# DE-150824.net
KiCad netlist of a schematic drawn in Altium Designer
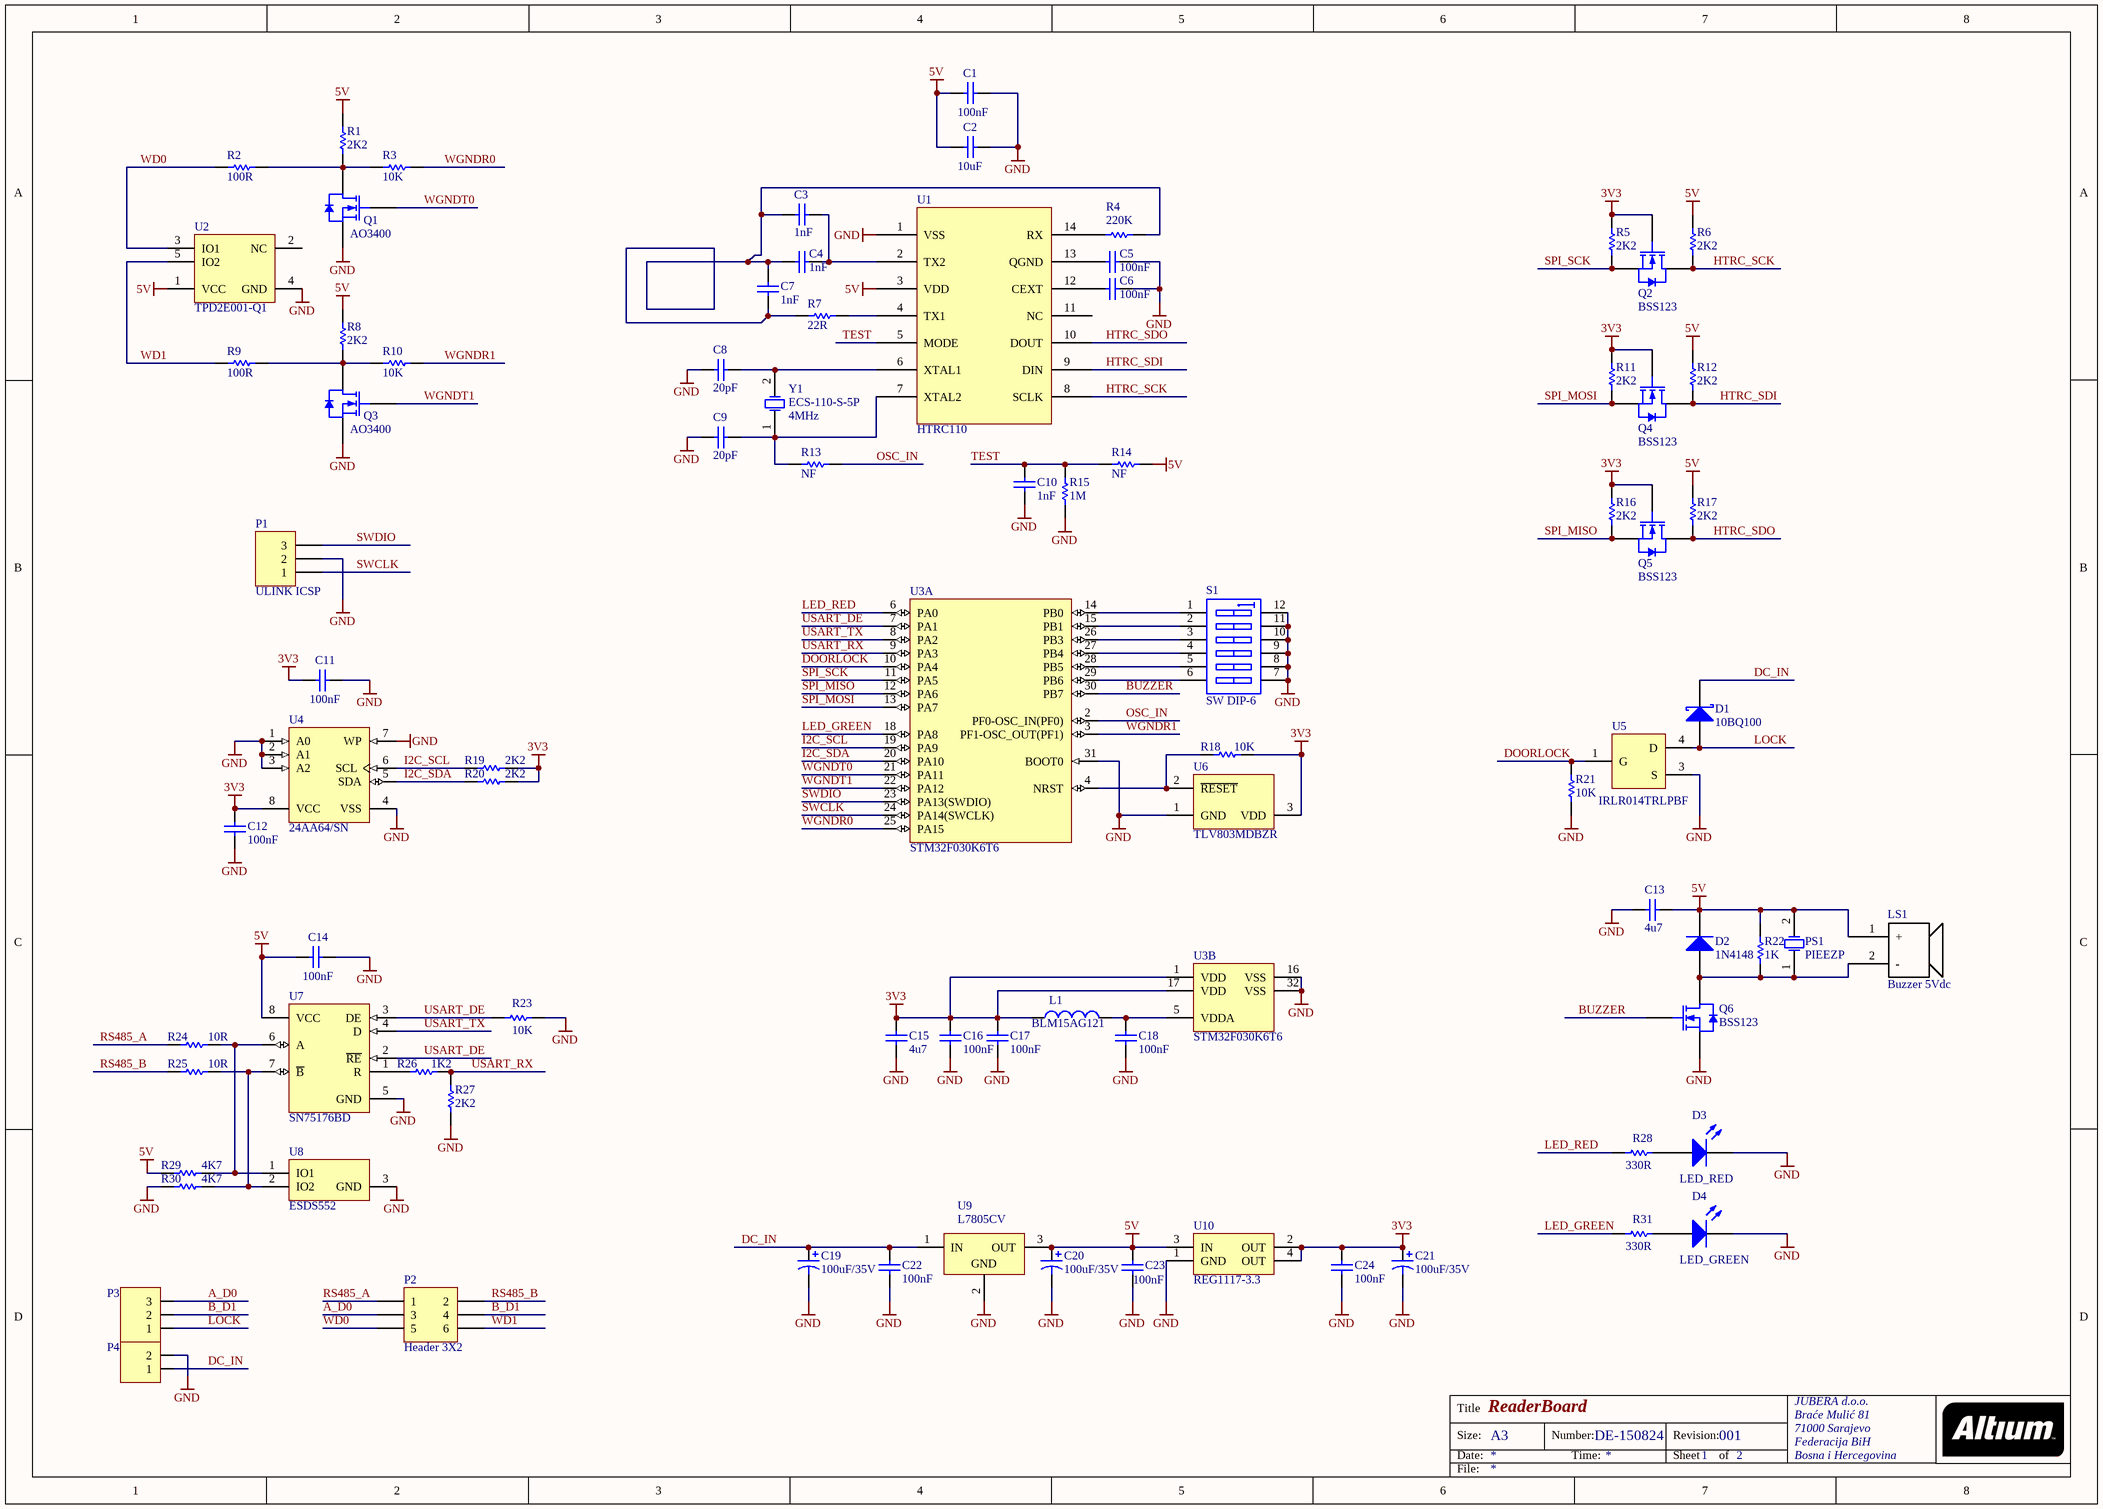
[diagram p0: DE-150824.SchDoc]

(export (version "E")
  (design (tool "Eeschema 10.0.6"))
  (components
    (comp (ref "C1")
      (value "100nF")
      (footprint "0603")
      (description "Ceramic Chip Capacitor - Standard")
      (fields (field (name "Comment") "C0603") (field (name "PUBLISHER") "Altium Limited"))
      (libsource (lib "DE-150824") (part "C0603"))
    )
    (comp (ref "C2")
      (value "10uF")
      (footprint "0805")
      (description "Ceramic Chip Capacitor - Standard")
      (fields (field (name "Comment") "C0805") (field (name "PUBLISHER") "Altium Limited"))
      (libsource (lib "DE-150824") (part "C0805"))
    )
    (comp (ref "C3")
      (value "1nF")
      (footprint "VP31-2.5")
      (description "Dipped Radial Multilayer Ceramic Capacitor COG (NPO): 1pF, 50/63V")
      (fields (field (name "PUBLISHER") "Altium Limited"))
      (libsource (lib "Vishay Vitramon Ceramic Dipped Capacitor") (part "VP31BA1R0CA"))
    )
    (comp (ref "C4")
      (value "1nF")
      (footprint "0805")
      (description "Ceramic Chip Capacitor - Standard")
      (fields (field (name "Comment") "C0805") (field (name "PUBLISHER") "Altium Limited"))
      (libsource (lib "DE-150824") (part "C0805"))
    )
    (comp (ref "C5")
      (value "100nF")
      (footprint "0603")
      (description "Ceramic Chip Capacitor - Standard")
      (fields (field (name "Comment") "C0603") (field (name "PUBLISHER") "Altium Limited"))
      (libsource (lib "DE-150824") (part "C0603"))
    )
    (comp (ref "C6")
      (value "100nF")
      (footprint "0603")
      (description "Ceramic Chip Capacitor - Standard")
      (fields (field (name "Comment") "C0603") (field (name "PUBLISHER") "Altium Limited"))
      (libsource (lib "DE-150824") (part "C0603"))
    )
    (comp (ref "C7")
      (value "1nF")
      (footprint "0805")
      (description "Ceramic Chip Capacitor - Standard")
      (fields (field (name "Comment") "C0805") (field (name "PUBLISHER") "Altium Limited"))
      (libsource (lib "DE-150824") (part "C0805"))
    )
    (comp (ref "C8")
      (value "20pF")
      (footprint "0603")
      (description "Ceramic Chip Capacitor - Standard")
      (fields (field (name "PUBLISHER") "Altium Limited"))
      (libsource (lib "KEMET Chip Capacitor") (part "C0603"))
    )
    (comp (ref "C9")
      (value "20pF")
      (footprint "0603")
      (description "Ceramic Chip Capacitor - Standard")
      (fields (field (name "PUBLISHER") "Altium Limited"))
      (libsource (lib "KEMET Chip Capacitor") (part "C0603"))
    )
    (comp (ref "C10")
      (value "1nF")
      (footprint "0603")
      (description "Ceramic Chip Capacitor - Standard")
      (fields (field (name "Comment") "C0603") (field (name "PUBLISHER") "Altium Limited"))
      (libsource (lib "DE-150824") (part "C0603"))
    )
    (comp (ref "C11")
      (value "100nF")
      (footprint "0603")
      (description "Ceramic Chip Capacitor - Standard")
      (fields (field (name "Comment") "C0603") (field (name "PUBLISHER") "Altium Limited"))
      (libsource (lib "DE-150824") (part "C0603"))
    )
    (comp (ref "C12")
      (value "100nF")
      (footprint "0603")
      (description "Ceramic Chip Capacitor - Standard")
      (fields (field (name "Comment") "C0603") (field (name "PUBLISHER") "Altium Limited"))
      (libsource (lib "DE-150824") (part "C0603"))
    )
    (comp (ref "C13")
      (value "4u7")
      (footprint "0805")
      (description "Ceramic Chip Capacitor - Standard")
      (fields (field (name "Comment") "C0805") (field (name "PUBLISHER") "Altium Limited"))
      (libsource (lib "DE-150824") (part "C0805"))
    )
    (comp (ref "C14")
      (value "100nF")
      (footprint "0603")
      (description "Ceramic Chip Capacitor - Standard")
      (fields (field (name "Comment") "C0603") (field (name "PUBLISHER") "Altium Limited"))
      (libsource (lib "DE-150824") (part "C0603"))
    )
    (comp (ref "C15")
      (value "4u7")
      (footprint "0805")
      (description "Ceramic Chip Capacitor - Standard")
      (fields (field (name "Comment") "C0805") (field (name "PUBLISHER") "Altium Limited"))
      (libsource (lib "DE-150824") (part "C0805"))
    )
    (comp (ref "C16")
      (value "100nF")
      (footprint "0603")
      (description "Ceramic Chip Capacitor - Standard")
      (fields (field (name "Comment") "C0603") (field (name "PUBLISHER") "Altium Limited"))
      (libsource (lib "DE-150824") (part "C0603"))
    )
    (comp (ref "C17")
      (value "100nF")
      (footprint "0603")
      (description "Ceramic Chip Capacitor - Standard")
      (fields (field (name "Comment") "C0603") (field (name "PUBLISHER") "Altium Limited"))
      (libsource (lib "DE-150824") (part "C0603"))
    )
    (comp (ref "C18")
      (value "100nF")
      (footprint "0603")
      (description "Ceramic Chip Capacitor - Standard")
      (fields (field (name "Comment") "C0603") (field (name "PUBLISHER") "Altium Limited"))
      (libsource (lib "DE-150824") (part "C0603"))
    )
    (comp (ref "C19")
      (value "100uF/35V")
      (footprint "F")
      (fields (field (name "PUBLISHER") "Altium Limited"))
      (libsource (lib "Vishay Sprague Tantalum Chip Capacitor") (part "194D106X0015F2"))
    )
    (comp (ref "C20")
      (value "100uF/35V")
      (footprint "F")
      (fields (field (name "PUBLISHER") "Altium Limited"))
      (libsource (lib "Vishay Sprague Tantalum Chip Capacitor") (part "194D106X0015F2"))
    )
    (comp (ref "C21")
      (value "100uF/35V")
      (footprint "F")
      (fields (field (name "PUBLISHER") "Altium Limited"))
      (libsource (lib "Vishay Sprague Tantalum Chip Capacitor") (part "194D106X0015F2"))
    )
    (comp (ref "C22")
      (value "100nF")
      (footprint "0603")
      (description "Ceramic Chip Capacitor - Standard")
      (fields (field (name "Comment") "C0603") (field (name "PUBLISHER") "Altium Limited"))
      (libsource (lib "DE-150824") (part "C0603"))
    )
    (comp (ref "C23")
      (value "100nF")
      (footprint "0603")
      (description "Ceramic Chip Capacitor - Standard")
      (fields (field (name "Comment") "C0603") (field (name "PUBLISHER") "Altium Limited"))
      (libsource (lib "DE-150824") (part "C0603"))
    )
    (comp (ref "C24")
      (value "100nF")
      (footprint "0603")
      (description "Ceramic Chip Capacitor - Standard")
      (fields (field (name "Comment") "C0603") (field (name "PUBLISHER") "Altium Limited"))
      (libsource (lib "DE-150824") (part "C0603"))
    )
    (comp (ref "D1")
      (value "10BQ100")
      (footprint "SMB")
      (description "Schottky Rectifier")
      (fields (field (name "PUBLISHER") "Altium Limited"))
      (libsource (lib "DE-150824") (part "10BQ100"))
    )
    (comp (ref "D2")
      (value "1N4148")
      (footprint "SOD323")
      (description "General-purpose Diode")
      (fields (field (name "PUBLISHER") "Altium Limited"))
      (libsource (lib "DE-150824") (part "BAS321"))
    )
    (comp (ref "D3")
      (value "LED_RED")
      (footprint "1.6X0.8X0.8")
      (description "Blue Surface Mount Chip LED, Blue")
      (fields (field (name "PUBLISHER") "Altium Limited"))
      (libsource (lib "DE-150824") (part "HSMB-C190"))
    )
    (comp (ref "D4")
      (value "LED_GREEN")
      (footprint "1.6X0.8X0.8")
      (description "Blue Surface Mount Chip LED, Blue")
      (fields (field (name "PUBLISHER") "Altium Limited"))
      (libsource (lib "DE-150824") (part "HSMB-C190"))
    )
    (comp (ref "L1")
      (value "BLM15AG121")
      (footprint "0402-A")
      (description "SMD chip inductor")
      (fields (field (name "PUBLISHER") "Altium Limited"))
      (libsource (lib "DE-150824") (part "Chip inductor"))
    )
    (comp (ref "LS1")
      (value "Buzzer 5Vdc")
      (footprint "BUZZER")
      (description "5Vdc PCB buzzer")
      (libsource (lib "DE-150824") (part "BUZZER"))
    )
    (comp (ref "P1")
      (value "ULINK ICSP")
      (footprint "HDR1X3")
      (description "Header, 3-Pin")
      (fields (field (name "PUBLISHER") "Altium Limited"))
      (libsource (lib "DE-150824") (part "Header 3"))
    )
    (comp (ref "P2")
      (value "Header 3X2")
      (footprint "HDR2X3")
      (description "Header, 3-Pin, Dual row")
      (fields (field (name "PUBLISHER") "Altium Limited"))
      (libsource (lib "Miscellaneous Connectors") (part "Header 3X2"))
    )
    (comp (ref "P3")
      (value "3 pin terminal")
      (footprint "3 PIN TERMINAL BLOCK  3,5mm")
      (description "3 pinski terminal blok konektor")
      (libsource (lib "DE-150824") (part "TERMINAL BLOK 3"))
    )
    (comp (ref "P4")
      (value "2 pin terminal")
      (footprint "2 PIN TERMINAL BLOCK 3,5mm")
      (description "Terminal blok konektor 3,5 mm")
      (libsource (lib "DE-150824") (part "TERMINAL BLOK 2"))
    )
    (comp (ref "PS1")
      (value "PIEEZP")
      (footprint "PKM13EPYH4000-A0")
      (description "Surface Mount Quartz Crystal")
      (fields (field (name "PUBLISHER") "Altium Limited"))
      (libsource (lib "DE-150824") (part "PKM13EPYH4000-A0"))
    )
    (comp (ref "Q1")
      (value "AO3400")
      (footprint "SOT23_N")
      (description "N-channel Enhancement Mode Vertical D-MOSFET")
      (fields (field (name "PUBLISHER") "Altium Limited"))
      (libsource (lib "DE-150824") (part "BSS123"))
    )
    (comp (ref "Q2")
      (value "BSS123")
      (footprint "SOT23_N")
      (description "N-channel Enhancement Mode Vertical D-MOSFET")
      (fields (field (name "PUBLISHER") "Altium Limited"))
      (libsource (lib "DE-150824") (part "BSS123"))
    )
    (comp (ref "Q3")
      (value "AO3400")
      (footprint "SOT23_N")
      (description "N-channel Enhancement Mode Vertical D-MOSFET")
      (fields (field (name "PUBLISHER") "Altium Limited"))
      (libsource (lib "DE-150824") (part "BSS123"))
    )
    (comp (ref "Q4")
      (value "BSS123")
      (footprint "SOT23_N")
      (description "N-channel Enhancement Mode Vertical D-MOSFET")
      (fields (field (name "PUBLISHER") "Altium Limited"))
      (libsource (lib "DE-150824") (part "BSS123"))
    )
    (comp (ref "Q5")
      (value "BSS123")
      (footprint "SOT23_N")
      (description "N-channel Enhancement Mode Vertical D-MOSFET")
      (fields (field (name "PUBLISHER") "Altium Limited"))
      (libsource (lib "DE-150824") (part "BSS123"))
    )
    (comp (ref "Q6")
      (value "BSS123")
      (footprint "SOT23_N")
      (description "N-channel Enhancement Mode Vertical D-MOSFET")
      (fields (field (name "PUBLISHER") "Altium Limited"))
      (libsource (lib "DE-150824") (part "BSS123"))
    )
    (comp (ref "R1")
      (value "2K2")
      (footprint "ERA-0805")
      (fields (field (name "PUBLISHER") "Altium Limited"))
      (libsource (lib "DE-150824") (part "ERAS"))
    )
    (comp (ref "R2")
      (value "100R")
      (footprint "ERA-0805")
      (fields (field (name "PUBLISHER") "Altium Limited"))
      (libsource (lib "DE-150824") (part "ERAS"))
    )
    (comp (ref "R3")
      (value "10K")
      (footprint "ERA-0805")
      (fields (field (name "PUBLISHER") "Altium Limited"))
      (libsource (lib "DE-150824") (part "ERAS"))
    )
    (comp (ref "R4")
      (value "220K")
      (footprint "ERA-0805")
      (fields (field (name "PUBLISHER") "Altium Limited"))
      (libsource (lib "DE-150824") (part "ERAS"))
    )
    (comp (ref "R5")
      (value "2K2")
      (footprint "ERA-0603")
      (fields (field (name "PUBLISHER") "Altium Limited"))
      (libsource (lib "DE-150824") (part "ERAV"))
    )
    (comp (ref "R6")
      (value "2K2")
      (footprint "ERA-0603")
      (fields (field (name "PUBLISHER") "Altium Limited"))
      (libsource (lib "DE-150824") (part "ERAV"))
    )
    (comp (ref "R7")
      (value "22R")
      (footprint "ERA-0805")
      (fields (field (name "PUBLISHER") "Altium Limited"))
      (libsource (lib "DE-150824") (part "ERAS"))
    )
    (comp (ref "R8")
      (value "2K2")
      (footprint "ERA-0805")
      (fields (field (name "PUBLISHER") "Altium Limited"))
      (libsource (lib "DE-150824") (part "ERAS"))
    )
    (comp (ref "R9")
      (value "100R")
      (footprint "ERA-0805")
      (fields (field (name "PUBLISHER") "Altium Limited"))
      (libsource (lib "DE-150824") (part "ERAS"))
    )
    (comp (ref "R10")
      (value "10K")
      (footprint "ERA-0805")
      (fields (field (name "PUBLISHER") "Altium Limited"))
      (libsource (lib "DE-150824") (part "ERAS"))
    )
    (comp (ref "R11")
      (value "2K2")
      (footprint "ERA-0603")
      (fields (field (name "PUBLISHER") "Altium Limited"))
      (libsource (lib "DE-150824") (part "ERAV"))
    )
    (comp (ref "R12")
      (value "2K2")
      (footprint "ERA-0603")
      (fields (field (name "PUBLISHER") "Altium Limited"))
      (libsource (lib "DE-150824") (part "ERAV"))
    )
    (comp (ref "R13")
      (value "NF")
      (footprint "ERA-0805")
      (fields (field (name "PUBLISHER") "Altium Limited"))
      (libsource (lib "DE-150824") (part "ERAS"))
    )
    (comp (ref "R14")
      (value "NF")
      (footprint "ERA-0805")
      (fields (field (name "PUBLISHER") "Altium Limited"))
      (libsource (lib "DE-150824") (part "ERAS"))
    )
    (comp (ref "R15")
      (value "1M")
      (footprint "ERA-0805")
      (fields (field (name "PUBLISHER") "Altium Limited"))
      (libsource (lib "DE-150824") (part "ERAS"))
    )
    (comp (ref "R16")
      (value "2K2")
      (footprint "ERA-0603")
      (fields (field (name "PUBLISHER") "Altium Limited"))
      (libsource (lib "DE-150824") (part "ERAV"))
    )
    (comp (ref "R17")
      (value "2K2")
      (footprint "ERA-0603")
      (fields (field (name "PUBLISHER") "Altium Limited"))
      (libsource (lib "DE-150824") (part "ERAV"))
    )
    (comp (ref "R18")
      (value "10K")
      (footprint "ERA-0603")
      (fields (field (name "PUBLISHER") "Altium Limited"))
      (libsource (lib "DE-150824") (part "ERAV"))
    )
    (comp (ref "R19")
      (value "2K2")
      (footprint "ERA-0603")
      (fields (field (name "PUBLISHER") "Altium Limited"))
      (libsource (lib "DE-150824") (part "ERAV"))
    )
    (comp (ref "R20")
      (value "2K2")
      (footprint "ERA-0603")
      (fields (field (name "PUBLISHER") "Altium Limited"))
      (libsource (lib "DE-150824") (part "ERAV"))
    )
    (comp (ref "R21")
      (value "10K")
      (footprint "ERA-0603")
      (fields (field (name "PUBLISHER") "Altium Limited"))
      (libsource (lib "DE-150824") (part "ERAV"))
    )
    (comp (ref "R22")
      (value "1K")
      (footprint "ERA-0603")
      (fields (field (name "PUBLISHER") "Altium Limited"))
      (libsource (lib "DE-150824") (part "ERAV"))
    )
    (comp (ref "R23")
      (value "10K")
      (footprint "ERA-0603")
      (fields (field (name "PUBLISHER") "Altium Limited"))
      (libsource (lib "DE-150824") (part "ERAV"))
    )
    (comp (ref "R24")
      (value "10R")
      (footprint "ERA-0805")
      (fields (field (name "PUBLISHER") "Altium Limited"))
      (libsource (lib "DE-150824") (part "ERAS"))
    )
    (comp (ref "R25")
      (value "10R")
      (footprint "ERA-0805")
      (fields (field (name "PUBLISHER") "Altium Limited"))
      (libsource (lib "DE-150824") (part "ERAS"))
    )
    (comp (ref "R26")
      (value "1K2")
      (footprint "ERA-0603")
      (fields (field (name "PUBLISHER") "Altium Limited"))
      (libsource (lib "DE-150824") (part "ERAV"))
    )
    (comp (ref "R27")
      (value "2K2")
      (footprint "ERA-0603")
      (fields (field (name "PUBLISHER") "Altium Limited"))
      (libsource (lib "DE-150824") (part "ERAV"))
    )
    (comp (ref "R28")
      (value "330R")
      (footprint "ERA-0603")
      (fields (field (name "PUBLISHER") "Altium Limited"))
      (libsource (lib "DE-150824") (part "ERAV"))
    )
    (comp (ref "R29")
      (value "4K7")
      (footprint "ERA-0603")
      (fields (field (name "PUBLISHER") "Altium Limited"))
      (libsource (lib "DE-150824") (part "ERAV"))
    )
    (comp (ref "R30")
      (value "4K7")
      (footprint "ERA-0603")
      (fields (field (name "PUBLISHER") "Altium Limited"))
      (libsource (lib "DE-150824") (part "ERAV"))
    )
    (comp (ref "R31")
      (value "330R")
      (footprint "ERA-0603")
      (fields (field (name "PUBLISHER") "Altium Limited"))
      (libsource (lib "DE-150824") (part "ERAV"))
    )
    (comp (ref "S1")
      (value "SW DIP-6")
      (footprint "DIP-12/SW")
      (description "DIP Switch, 6 Position, SPST")
      (fields (field (name "PUBLISHER") "Altium Limited"))
      (libsource (lib "Miscellaneous Devices") (part "SW DIP-6"))
    )
    (comp (ref "U1")
      (value "HTRC110")
      (footprint "SOIC-SL14_N")
      (description "HITAG reader chip")
      (libsource (lib "DE-150824") (part "HTRC110"))
    )
    (comp (ref "U2")
      (value "TPD2E001-Q1")
      (footprint "DRL5_V")
      (fields (field (name "MANUFACTURER") "Texas Instruments") (field (name "PARTNUMBER") "TPD2E001IDRLRQ1"))
      (libsource (lib "TI Interface ESD EMI Protection") (part "TPD2E001IDRLRQ1"))
    )
    (comp (ref "U3")
      (value "STM32F030K6T6")
      (footprint "STM-LQFP32_N")
      (libsource (lib "STMicroelectronics STM32 F0") (part "STM32F030K6T6"))
    )
    (comp (ref "U4")
      (value "24AA64/SN")
      (footprint "SOIC-SN8_N")
      (description "64Kbit, 400kHz, 1.7V, I2C Serial EEPROM, 8-Pin SOIC 150mil, Commercial Temperature")
      (fields (field (name "PUBLISHER") "Altium Limited"))
      (libsource (lib "DE-150824") (part "24AA64/SN"))
    )
    (comp (ref "U5")
      (value "IRLR014TRLPBF")
      (footprint "ONSC-DPAK-3-369C-01_V")
      (fields (field (name "MANUFACTURER") "On Semiconductor") (field (name "PARTNUMBER") "NCV8408DTRKG"))
      (libsource (lib "ON Semi Protected MOSFETs") (part "NCV8408DTRKG"))
    )
    (comp (ref "U6")
      (value "TLV803MDBZR")
      (footprint "DBZ3_N")
      (fields (field (name "MANUFACTURER") "Texas Instruments"))
      (libsource (lib "TI Power Management Supervisor and Reset IC") (part "TLV803MDBZR"))
    )
    (comp (ref "U7")
      (value "SN75176BD")
      (footprint "D008_N")
      (description "Differential Bus Transceiver")
      (fields (field (name "PUBLISHER") "Altium Limited"))
      (libsource (lib "DE-150824") (part "SN75176BD"))
    )
    (comp (ref "U8")
      (value "ESDS552")
      (footprint "DCK3_N")
      (fields (field (name "MANUFACTURER") "Texas Instruments") (field (name "PARTNUMBER") "TPD2E007DCKR"))
      (libsource (lib "TI Interface ESD EMI Protection") (part "TPD2E007DCKR"))
    )
    (comp (ref "U9")
      (value "L7805CV")
      (footprint "TO220")
      (description "Positive Voltage Regulator, 5V, 3-Pin TO-220")
      (libsource (lib "DE-150824") (part "L7805CV"))
    )
    (comp (ref "U10")
      (value "REG1117-3.3")
      (footprint "ZZ311")
      (description "800mA and 1A Low Dropout Positive Regulator 2.85V, 3.3V, 5V, and Adjustable")
      (fields (field (name "PUBLISHER") "Altium Limited"))
      (libsource (lib "DE-080324") (part "REG1117-3.3"))
    )
    (comp (ref "Y1")
      (value "ECS-110-S-5P")
      (footprint "CSM-7")
      (description "Crystal Oscillator")
      (fields (field (name "ALTIUM_VALUE") "4MHz") (field (name "PUBLISHER") "Altium Limited"))
      (libsource (lib "ECS Crystal Oscillator") (part "ECS-110-S-5P"))
    )
  )
  (nets
    (net (code "1") (name "/A_D0") (class "Default")
      (node (ref "P2") (pin "3") (pinfunction "3_3") (pintype "passive"))
      (node (ref "P3") (pin "3") (pinfunction "3_3") (pintype "passive"))
    )
    (net (code "2") (name "/BUZZER") (class "Default")
      (node (ref "Q6") (pin "1") (pinfunction "G_1") (pintype "passive"))
      (node (ref "U3") (pin "30") (pinfunction "PB7_30") (pintype "bidirectional"))
    )
    (net (code "3") (name "/B_D1") (class "Default")
      (node (ref "P2") (pin "4") (pinfunction "4_4") (pintype "passive"))
      (node (ref "P3") (pin "2") (pinfunction "2_2") (pintype "passive"))
    )
    (net (code "4") (name "/DC_IN") (class "Default")
      (node (ref "C19") (pin "1") (pinfunction "1_1") (pintype "passive"))
      (node (ref "C22") (pin "2") (pinfunction "2_2") (pintype "passive"))
      (node (ref "D1") (pin "2") (pinfunction "K_2") (pintype "passive"))
      (node (ref "P4") (pin "1") (pinfunction "1_1") (pintype "passive"))
      (node (ref "U9") (pin "1") (pinfunction "IN_1") (pintype "power_in"))
    )
    (net (code "5") (name "/DOORLOCK") (class "Default")
      (node (ref "R21") (pin "1") (pinfunction "1_1") (pintype "passive"))
      (node (ref "U3") (pin "10") (pinfunction "PA4_10") (pintype "bidirectional"))
      (node (ref "U5") (pin "1") (pinfunction "G_1") (pintype "passive"))
    )
    (net (code "6") (name "/HTRC_SCK") (class "Default")
      (node (ref "Q2") (pin "3") (pinfunction "D_3") (pintype "passive"))
      (node (ref "R6") (pin "1") (pinfunction "1_1") (pintype "passive"))
      (node (ref "U1") (pin "8") (pinfunction "SCLK_8") (pintype "passive"))
    )
    (net (code "7") (name "/HTRC_SDI") (class "Default")
      (node (ref "Q4") (pin "3") (pinfunction "D_3") (pintype "passive"))
      (node (ref "R12") (pin "1") (pinfunction "1_1") (pintype "passive"))
      (node (ref "U1") (pin "9") (pinfunction "DIN_9") (pintype "passive"))
    )
    (net (code "8") (name "/HTRC_SDO") (class "Default")
      (node (ref "Q5") (pin "3") (pinfunction "D_3") (pintype "passive"))
      (node (ref "R17") (pin "1") (pinfunction "1_1") (pintype "passive"))
      (node (ref "U1") (pin "10") (pinfunction "DOUT_10") (pintype "passive"))
    )
    (net (code "9") (name "/I2C_SCL") (class "Default")
      (node (ref "R19") (pin "1") (pinfunction "1_1") (pintype "passive"))
      (node (ref "U3") (pin "19") (pinfunction "PA9_19") (pintype "bidirectional"))
      (node (ref "U4") (pin "6") (pinfunction "SCL_6") (pintype "input"))
    )
    (net (code "10") (name "/I2C_SDA") (class "Default")
      (node (ref "R20") (pin "1") (pinfunction "1_1") (pintype "passive"))
      (node (ref "U3") (pin "20") (pinfunction "PA10_20") (pintype "bidirectional"))
      (node (ref "U4") (pin "5") (pinfunction "SDA_5") (pintype "bidirectional"))
    )
    (net (code "11") (name "/LED_GREEN") (class "Default")
      (node (ref "R31") (pin "1") (pinfunction "1_1") (pintype "passive"))
      (node (ref "U3") (pin "18") (pinfunction "PA8_18") (pintype "bidirectional"))
    )
    (net (code "12") (name "/LED_RED") (class "Default")
      (node (ref "R28") (pin "1") (pinfunction "1_1") (pintype "passive"))
      (node (ref "U3") (pin "6") (pinfunction "PA0_6") (pintype "bidirectional"))
    )
    (net (code "13") (name "/LOCK") (class "Default")
      (node (ref "D1") (pin "1") (pinfunction "A_1") (pintype "passive"))
      (node (ref "P3") (pin "1") (pinfunction "1_1") (pintype "passive"))
      (node (ref "U5") (pin "4") (pinfunction "D_4") (pintype "passive"))
    )
    (net (code "14") (name "/OSC_IN") (class "Default")
      (node (ref "R13") (pin "2") (pinfunction "2_2") (pintype "passive"))
      (node (ref "U3") (pin "2") (pinfunction "PF0-OSC_IN(PF0)_2") (pintype "bidirectional"))
    )
    (net (code "15") (name "/RS485_A") (class "Default")
      (node (ref "P2") (pin "1") (pinfunction "1_1") (pintype "passive"))
      (node (ref "R24") (pin "1") (pinfunction "1_1") (pintype "passive"))
    )
    (net (code "16") (name "/RS485_B") (class "Default")
      (node (ref "P2") (pin "2") (pinfunction "2_2") (pintype "passive"))
      (node (ref "R25") (pin "1") (pinfunction "1_1") (pintype "passive"))
    )
    (net (code "17") (name "/SPI_MISO") (class "Default")
      (node (ref "Q5") (pin "2") (pinfunction "S_2") (pintype "passive"))
      (node (ref "R16") (pin "1") (pinfunction "1_1") (pintype "passive"))
      (node (ref "U3") (pin "12") (pinfunction "PA6_12") (pintype "bidirectional"))
    )
    (net (code "18") (name "/SPI_MOSI") (class "Default")
      (node (ref "Q4") (pin "2") (pinfunction "S_2") (pintype "passive"))
      (node (ref "R11") (pin "1") (pinfunction "1_1") (pintype "passive"))
      (node (ref "U3") (pin "13") (pinfunction "PA7_13") (pintype "bidirectional"))
    )
    (net (code "19") (name "/SPI_SCK") (class "Default")
      (node (ref "Q2") (pin "2") (pinfunction "S_2") (pintype "passive"))
      (node (ref "R5") (pin "1") (pinfunction "1_1") (pintype "passive"))
      (node (ref "U3") (pin "11") (pinfunction "PA5_11") (pintype "bidirectional"))
    )
    (net (code "20") (name "/SWCLK") (class "Default")
      (node (ref "P1") (pin "1") (pinfunction "1_1") (pintype "passive"))
      (node (ref "U3") (pin "24") (pinfunction "PA14(SWCLK)_24") (pintype "bidirectional"))
    )
    (net (code "21") (name "/SWDIO") (class "Default")
      (node (ref "P1") (pin "3") (pinfunction "3_3") (pintype "passive"))
      (node (ref "U3") (pin "23") (pinfunction "PA13(SWDIO)_23") (pintype "bidirectional"))
    )
    (net (code "22") (name "/TEST") (class "Default")
      (node (ref "C10") (pin "1") (pinfunction "1_1") (pintype "passive"))
      (node (ref "R14") (pin "1") (pinfunction "1_1") (pintype "passive"))
      (node (ref "R15") (pin "2") (pinfunction "2_2") (pintype "passive"))
      (node (ref "U1") (pin "5") (pinfunction "MODE_5") (pintype "passive"))
    )
    (net (code "23") (name "/USART_DE") (class "Default")
      (node (ref "R23") (pin "1") (pinfunction "1_1") (pintype "passive"))
      (node (ref "U3") (pin "7") (pinfunction "PA1_7") (pintype "bidirectional"))
      (node (ref "U7") (pin "2") (pinfunction "~{RE}_2") (pintype "input"))
      (node (ref "U7") (pin "3") (pinfunction "DE_3") (pintype "input"))
    )
    (net (code "24") (name "/USART_RX") (class "Default")
      (node (ref "R26") (pin "2") (pinfunction "2_2") (pintype "passive"))
      (node (ref "R27") (pin "2") (pinfunction "2_2") (pintype "passive"))
      (node (ref "U3") (pin "9") (pinfunction "PA3_9") (pintype "bidirectional"))
    )
    (net (code "25") (name "/USART_TX") (class "Default")
      (node (ref "U3") (pin "8") (pinfunction "PA2_8") (pintype "bidirectional"))
      (node (ref "U7") (pin "4") (pinfunction "D_4") (pintype "input"))
    )
    (net (code "26") (name "/WD0") (class "Default")
      (node (ref "P2") (pin "5") (pinfunction "5_5") (pintype "passive"))
      (node (ref "R2") (pin "2") (pinfunction "2_2") (pintype "passive"))
      (node (ref "U2") (pin "3") (pinfunction "IO1_3") (pintype "passive"))
    )
    (net (code "27") (name "/WD1") (class "Default")
      (node (ref "P2") (pin "6") (pinfunction "6_6") (pintype "passive"))
      (node (ref "R9") (pin "2") (pinfunction "2_2") (pintype "passive"))
      (node (ref "U2") (pin "5") (pinfunction "IO2_5") (pintype "passive"))
    )
    (net (code "28") (name "/WGNDR0") (class "Default")
      (node (ref "R3") (pin "1") (pinfunction "1_1") (pintype "passive"))
      (node (ref "U3") (pin "25") (pinfunction "PA15_25") (pintype "bidirectional"))
    )
    (net (code "29") (name "/WGNDR1") (class "Default")
      (node (ref "R10") (pin "1") (pinfunction "1_1") (pintype "passive"))
      (node (ref "U3") (pin "3") (pinfunction "PF1-OSC_OUT(PF1)_3") (pintype "bidirectional"))
    )
    (net (code "30") (name "/WGNDT0") (class "Default")
      (node (ref "Q1") (pin "1") (pinfunction "G_1") (pintype "passive"))
      (node (ref "U3") (pin "21") (pinfunction "PA11_21") (pintype "bidirectional"))
    )
    (net (code "31") (name "/WGNDT1") (class "Default")
      (node (ref "Q3") (pin "1") (pinfunction "G_1") (pintype "passive"))
      (node (ref "U3") (pin "22") (pinfunction "PA12_22") (pintype "bidirectional"))
    )
    (net (code "32") (name "3V3") (class "Default")
      (node (ref "C11") (pin "2") (pinfunction "2_2") (pintype "passive"))
      (node (ref "C12") (pin "2") (pinfunction "2_2") (pintype "passive"))
      (node (ref "C15") (pin "2") (pinfunction "2_2") (pintype "passive"))
      (node (ref "C16") (pin "2") (pinfunction "2_2") (pintype "passive"))
      (node (ref "C17") (pin "2") (pinfunction "2_2") (pintype "passive"))
      (node (ref "C21") (pin "1") (pinfunction "1_1") (pintype "passive"))
      (node (ref "C24") (pin "2") (pinfunction "2_2") (pintype "passive"))
      (node (ref "L1") (pin "1") (pinfunction "1_1") (pintype "passive"))
      (node (ref "Q2") (pin "1") (pinfunction "G_1") (pintype "passive"))
      (node (ref "Q4") (pin "1") (pinfunction "G_1") (pintype "passive"))
      (node (ref "Q5") (pin "1") (pinfunction "G_1") (pintype "passive"))
      (node (ref "R11") (pin "2") (pinfunction "2_2") (pintype "passive"))
      (node (ref "R16") (pin "2") (pinfunction "2_2") (pintype "passive"))
      (node (ref "R18") (pin "1") (pinfunction "1_1") (pintype "passive"))
      (node (ref "R19") (pin "2") (pinfunction "2_2") (pintype "passive"))
      (node (ref "R20") (pin "2") (pinfunction "2_2") (pintype "passive"))
      (node (ref "R5") (pin "2") (pinfunction "2_2") (pintype "passive"))
      (node (ref "U10") (pin "2") (pinfunction "OUT_2") (pintype "power_in"))
      (node (ref "U10") (pin "4") (pinfunction "OUT_4") (pintype "power_in"))
      (node (ref "U3") (pin "1") (pinfunction "VDD_1") (pintype "power_in"))
      (node (ref "U3") (pin "17") (pinfunction "VDD_17") (pintype "power_in"))
      (node (ref "U4") (pin "8") (pinfunction "VCC_8") (pintype "power_in"))
      (node (ref "U6") (pin "3") (pinfunction "VDD_3") (pintype "power_in"))
    )
    (net (code "33") (name "5V") (class "Default")
      (node (ref "C1") (pin "2") (pinfunction "2_2") (pintype "passive"))
      (node (ref "C13") (pin "1") (pinfunction "1_1") (pintype "passive"))
      (node (ref "C14") (pin "2") (pinfunction "2_2") (pintype "passive"))
      (node (ref "C2") (pin "2") (pinfunction "2_2") (pintype "passive"))
      (node (ref "C20") (pin "1") (pinfunction "1_1") (pintype "passive"))
      (node (ref "C23") (pin "2") (pinfunction "2_2") (pintype "passive"))
      (node (ref "D2") (pin "1") (pinfunction "K_1") (pintype "passive"))
      (node (ref "LS1") (pin "1") (pinfunction "+_1") (pintype "passive"))
      (node (ref "PS1") (pin "2") (pinfunction "OSC2_2") (pintype "passive"))
      (node (ref "R1") (pin "2") (pinfunction "2_2") (pintype "passive"))
      (node (ref "R12") (pin "2") (pinfunction "2_2") (pintype "passive"))
      (node (ref "R14") (pin "2") (pinfunction "2_2") (pintype "passive"))
      (node (ref "R17") (pin "2") (pinfunction "2_2") (pintype "passive"))
      (node (ref "R22") (pin "1") (pinfunction "1_1") (pintype "passive"))
      (node (ref "R29") (pin "1") (pinfunction "1_1") (pintype "passive"))
      (node (ref "R6") (pin "2") (pinfunction "2_2") (pintype "passive"))
      (node (ref "R8") (pin "2") (pinfunction "2_2") (pintype "passive"))
      (node (ref "U1") (pin "3") (pinfunction "VDD_3") (pintype "passive"))
      (node (ref "U10") (pin "3") (pinfunction "IN_3") (pintype "power_in"))
      (node (ref "U2") (pin "1") (pinfunction "VCC_1") (pintype "power_in"))
      (node (ref "U7") (pin "8") (pinfunction "VCC_8") (pintype "power_in"))
      (node (ref "U9") (pin "3") (pinfunction "OUT_3") (pintype "power_in"))
    )
    (net (code "34") (name "GND") (class "Default")
      (node (ref "C1") (pin "1") (pinfunction "1_1") (pintype "passive"))
      (node (ref "C10") (pin "2") (pinfunction "2_2") (pintype "passive"))
      (node (ref "C11") (pin "1") (pinfunction "1_1") (pintype "passive"))
      (node (ref "C12") (pin "1") (pinfunction "1_1") (pintype "passive"))
      (node (ref "C13") (pin "2") (pinfunction "2_2") (pintype "passive"))
      (node (ref "C14") (pin "1") (pinfunction "1_1") (pintype "passive"))
      (node (ref "C15") (pin "1") (pinfunction "1_1") (pintype "passive"))
      (node (ref "C16") (pin "1") (pinfunction "1_1") (pintype "passive"))
      (node (ref "C17") (pin "1") (pinfunction "1_1") (pintype "passive"))
      (node (ref "C18") (pin "1") (pinfunction "1_1") (pintype "passive"))
      (node (ref "C19") (pin "2") (pinfunction "2_2") (pintype "passive"))
      (node (ref "C2") (pin "1") (pinfunction "1_1") (pintype "passive"))
      (node (ref "C20") (pin "2") (pinfunction "2_2") (pintype "passive"))
      (node (ref "C21") (pin "2") (pinfunction "2_2") (pintype "passive"))
      (node (ref "C22") (pin "1") (pinfunction "1_1") (pintype "passive"))
      (node (ref "C23") (pin "1") (pinfunction "1_1") (pintype "passive"))
      (node (ref "C24") (pin "1") (pinfunction "1_1") (pintype "passive"))
      (node (ref "C5") (pin "1") (pinfunction "1_1") (pintype "passive"))
      (node (ref "C6") (pin "1") (pinfunction "1_1") (pintype "passive"))
      (node (ref "C8") (pin "1") (pinfunction "1_1") (pintype "passive"))
      (node (ref "C9") (pin "1") (pinfunction "1_1") (pintype "passive"))
      (node (ref "D3") (pin "2") (pinfunction "K_2") (pintype "passive"))
      (node (ref "D4") (pin "2") (pinfunction "K_2") (pintype "passive"))
      (node (ref "P1") (pin "2") (pinfunction "2_2") (pintype "passive"))
      (node (ref "P4") (pin "2") (pinfunction "2_2") (pintype "passive"))
      (node (ref "Q1") (pin "2") (pinfunction "S_2") (pintype "passive"))
      (node (ref "Q3") (pin "2") (pinfunction "S_2") (pintype "passive"))
      (node (ref "Q6") (pin "2") (pinfunction "S_2") (pintype "passive"))
      (node (ref "R15") (pin "1") (pinfunction "1_1") (pintype "passive"))
      (node (ref "R21") (pin "2") (pinfunction "2_2") (pintype "passive"))
      (node (ref "R23") (pin "2") (pinfunction "2_2") (pintype "passive"))
      (node (ref "R27") (pin "1") (pinfunction "1_1") (pintype "passive"))
      (node (ref "R30") (pin "1") (pinfunction "1_1") (pintype "passive"))
      (node (ref "S1") (pin "10") (pinfunction "B3_10") (pintype "passive"))
      (node (ref "S1") (pin "11") (pinfunction "B2_11") (pintype "passive"))
      (node (ref "S1") (pin "12") (pinfunction "B1_12") (pintype "passive"))
      (node (ref "S1") (pin "7") (pinfunction "B6_7") (pintype "passive"))
      (node (ref "S1") (pin "8") (pinfunction "B5_8") (pintype "passive"))
      (node (ref "S1") (pin "9") (pinfunction "B4_9") (pintype "passive"))
      (node (ref "U1") (pin "1") (pinfunction "VSS_1") (pintype "passive"))
      (node (ref "U10") (pin "1") (pinfunction "GND_1") (pintype "power_in"))
      (node (ref "U2") (pin "4") (pinfunction "GND_4") (pintype "power_in"))
      (node (ref "U3") (pin "16") (pinfunction "VSS_16") (pintype "power_in"))
      (node (ref "U3") (pin "31") (pinfunction "BOOT0_31") (pintype "input"))
      (node (ref "U3") (pin "32") (pinfunction "VSS_32") (pintype "power_in"))
      (node (ref "U4") (pin "1") (pinfunction "A0_1") (pintype "input"))
      (node (ref "U4") (pin "2") (pinfunction "A1_2") (pintype "input"))
      (node (ref "U4") (pin "3") (pinfunction "A2_3") (pintype "input"))
      (node (ref "U4") (pin "4") (pinfunction "VSS_4") (pintype "power_in"))
      (node (ref "U4") (pin "7") (pinfunction "WP_7") (pintype "input"))
      (node (ref "U5") (pin "3") (pinfunction "S_3") (pintype "passive"))
      (node (ref "U6") (pin "1") (pinfunction "GND_1") (pintype "power_in"))
      (node (ref "U7") (pin "5") (pinfunction "GND_5") (pintype "power_in"))
      (node (ref "U8") (pin "3") (pinfunction "GND_3") (pintype "power_in"))
      (node (ref "U9") (pin "2") (pinfunction "GND_2") (pintype "power_in"))
    )
    (net (code "35") (name "Net-(C3-Pad1)") (class "Default")
      (node (ref "C3") (pin "1") (pinfunction "1_1") (pintype "passive"))
      (node (ref "C4") (pin "2") (pinfunction "2_2") (pintype "passive"))
      (node (ref "C7") (pin "1") (pinfunction "1_1") (pintype "passive"))
      (node (ref "C7") (pin "2") (pinfunction "2_2") (pintype "passive"))
      (node (ref "R4") (pin "2") (pinfunction "2_2") (pintype "passive"))
      (node (ref "R7") (pin "1") (pinfunction "1_1") (pintype "passive"))
    )
    (net (code "36") (name "Net-(D2-A)") (class "Default")
      (node (ref "D2") (pin "2") (pinfunction "A_2") (pintype "passive"))
      (node (ref "LS1") (pin "2") (pinfunction "-_2") (pintype "passive"))
      (node (ref "PS1") (pin "1") (pinfunction "OSC1_1") (pintype "passive"))
      (node (ref "Q6") (pin "3") (pinfunction "D_3") (pintype "passive"))
      (node (ref "R22") (pin "2") (pinfunction "2_2") (pintype "passive"))
    )
    (net (code "37") (name "Net-(D3-A)") (class "Default")
      (node (ref "D3") (pin "1") (pinfunction "A_1") (pintype "passive"))
      (node (ref "R28") (pin "2") (pinfunction "2_2") (pintype "passive"))
    )
    (net (code "38") (name "Net-(D4-A)") (class "Default")
      (node (ref "D4") (pin "1") (pinfunction "A_1") (pintype "passive"))
      (node (ref "R31") (pin "2") (pinfunction "2_2") (pintype "passive"))
    )
    (net (code "39") (name "Net-(Q1-D)") (class "Default")
      (node (ref "Q1") (pin "3") (pinfunction "D_3") (pintype "passive"))
      (node (ref "R1") (pin "1") (pinfunction "1_1") (pintype "passive"))
      (node (ref "R2") (pin "1") (pinfunction "1_1") (pintype "passive"))
      (node (ref "R3") (pin "2") (pinfunction "2_2") (pintype "passive"))
    )
    (net (code "40") (name "Net-(Q3-D)") (class "Default")
      (node (ref "Q3") (pin "3") (pinfunction "D_3") (pintype "passive"))
      (node (ref "R10") (pin "2") (pinfunction "2_2") (pintype "passive"))
      (node (ref "R8") (pin "1") (pinfunction "1_1") (pintype "passive"))
      (node (ref "R9") (pin "1") (pinfunction "1_1") (pintype "passive"))
    )
    (net (code "41") (name "Net-(S1-A1)") (class "Default")
      (node (ref "S1") (pin "1") (pinfunction "A1_1") (pintype "passive"))
      (node (ref "U3") (pin "14") (pinfunction "PB0_14") (pintype "bidirectional"))
    )
    (net (code "42") (name "Net-(S1-A2)") (class "Default")
      (node (ref "S1") (pin "2") (pinfunction "A2_2") (pintype "passive"))
      (node (ref "U3") (pin "15") (pinfunction "PB1_15") (pintype "bidirectional"))
    )
    (net (code "43") (name "Net-(S1-A3)") (class "Default")
      (node (ref "S1") (pin "3") (pinfunction "A3_3") (pintype "passive"))
      (node (ref "U3") (pin "26") (pinfunction "PB3_26") (pintype "bidirectional"))
    )
    (net (code "44") (name "Net-(S1-A4)") (class "Default")
      (node (ref "S1") (pin "4") (pinfunction "A4_4") (pintype "passive"))
      (node (ref "U3") (pin "27") (pinfunction "PB4_27") (pintype "bidirectional"))
    )
    (net (code "45") (name "Net-(S1-A5)") (class "Default")
      (node (ref "S1") (pin "5") (pinfunction "A5_5") (pintype "passive"))
      (node (ref "U3") (pin "28") (pinfunction "PB5_28") (pintype "bidirectional"))
    )
    (net (code "46") (name "Net-(S1-A6)") (class "Default")
      (node (ref "S1") (pin "6") (pinfunction "A6_6") (pintype "passive"))
      (node (ref "U3") (pin "29") (pinfunction "PB6_29") (pintype "bidirectional"))
    )
    (net (code "47") (name "Net-(U1-CEXT)") (class "Default")
      (node (ref "C6") (pin "2") (pinfunction "2_2") (pintype "passive"))
      (node (ref "U1") (pin "12") (pinfunction "CEXT_12") (pintype "passive"))
    )
    (net (code "48") (name "Net-(U1-QGND)") (class "Default")
      (node (ref "C5") (pin "2") (pinfunction "2_2") (pintype "passive"))
      (node (ref "U1") (pin "13") (pinfunction "QGND_13") (pintype "passive"))
    )
    (net (code "49") (name "Net-(U1-RX)") (class "Default")
      (node (ref "R4") (pin "1") (pinfunction "1_1") (pintype "passive"))
      (node (ref "U1") (pin "14") (pinfunction "RX_14") (pintype "passive"))
    )
    (net (code "50") (name "Net-(U1-TX1)") (class "Default")
      (node (ref "R7") (pin "2") (pinfunction "2_2") (pintype "passive"))
      (node (ref "U1") (pin "4") (pinfunction "TX1_4") (pintype "passive"))
    )
    (net (code "51") (name "Net-(U1-TX2)") (class "Default")
      (node (ref "C3") (pin "2") (pinfunction "2_2") (pintype "passive"))
      (node (ref "C4") (pin "1") (pinfunction "1_1") (pintype "passive"))
      (node (ref "U1") (pin "2") (pinfunction "TX2_2") (pintype "passive"))
    )
    (net (code "52") (name "Net-(U1-XTAL1)") (class "Default")
      (node (ref "C8") (pin "2") (pinfunction "2_2") (pintype "passive"))
      (node (ref "U1") (pin "6") (pinfunction "XTAL1_6") (pintype "passive"))
      (node (ref "Y1") (pin "2") (pinfunction "OSC2_2") (pintype "passive"))
    )
    (net (code "53") (name "Net-(U1-XTAL2)") (class "Default")
      (node (ref "C9") (pin "2") (pinfunction "2_2") (pintype "passive"))
      (node (ref "R13") (pin "1") (pinfunction "1_1") (pintype "passive"))
      (node (ref "U1") (pin "7") (pinfunction "XTAL2_7") (pintype "passive"))
      (node (ref "Y1") (pin "1") (pinfunction "OSC1_1") (pintype "passive"))
    )
    (net (code "54") (name "Net-(U3A-NRST)") (class "Default")
      (node (ref "R18") (pin "2") (pinfunction "2_2") (pintype "passive"))
      (node (ref "U3") (pin "4") (pinfunction "NRST_4") (pintype "bidirectional"))
      (node (ref "U6") (pin "2") (pinfunction "~{RESET}_2") (pintype "open_collector"))
    )
    (net (code "55") (name "Net-(U3B-VDDA)") (class "Default")
      (node (ref "C18") (pin "2") (pinfunction "2_2") (pintype "passive"))
      (node (ref "L1") (pin "2") (pinfunction "2_2") (pintype "passive"))
      (node (ref "U3") (pin "5") (pinfunction "VDDA_5") (pintype "power_in"))
    )
    (net (code "56") (name "Net-(U7-A)") (class "Default")
      (node (ref "R24") (pin "2") (pinfunction "2_2") (pintype "passive"))
      (node (ref "R29") (pin "2") (pinfunction "2_2") (pintype "passive"))
      (node (ref "U7") (pin "6") (pinfunction "A_6") (pintype "bidirectional"))
      (node (ref "U8") (pin "1") (pinfunction "IO1_1") (pintype "passive"))
    )
    (net (code "57") (name "Net-(U7-R)") (class "Default")
      (node (ref "R26") (pin "1") (pinfunction "1_1") (pintype "passive"))
      (node (ref "U7") (pin "1") (pinfunction "R_1") (pintype "tri_state"))
    )
    (net (code "58") (name "Net-(U7-~{B})") (class "Default")
      (node (ref "R25") (pin "2") (pinfunction "2_2") (pintype "passive"))
      (node (ref "R30") (pin "2") (pinfunction "2_2") (pintype "passive"))
      (node (ref "U7") (pin "7") (pinfunction "~{B}_7") (pintype "bidirectional"))
      (node (ref "U8") (pin "2") (pinfunction "IO2_2") (pintype "passive"))
    )
    (net (code "59") (name "unconnected-(U1-NC-Pad11)") (class "Default")
      (node (ref "U1") (pin "11") (pinfunction "NC_11") (pintype "passive"))
    )
    (net (code "60") (name "unconnected-(U2-NC-Pad2)") (class "Default")
      (node (ref "U2") (pin "2") (pinfunction "NC_2") (pintype "passive"))
    )
  )
)
